# USB_OTG_FS.net
KiCad netlist of a schematic drawn in Altium Designer
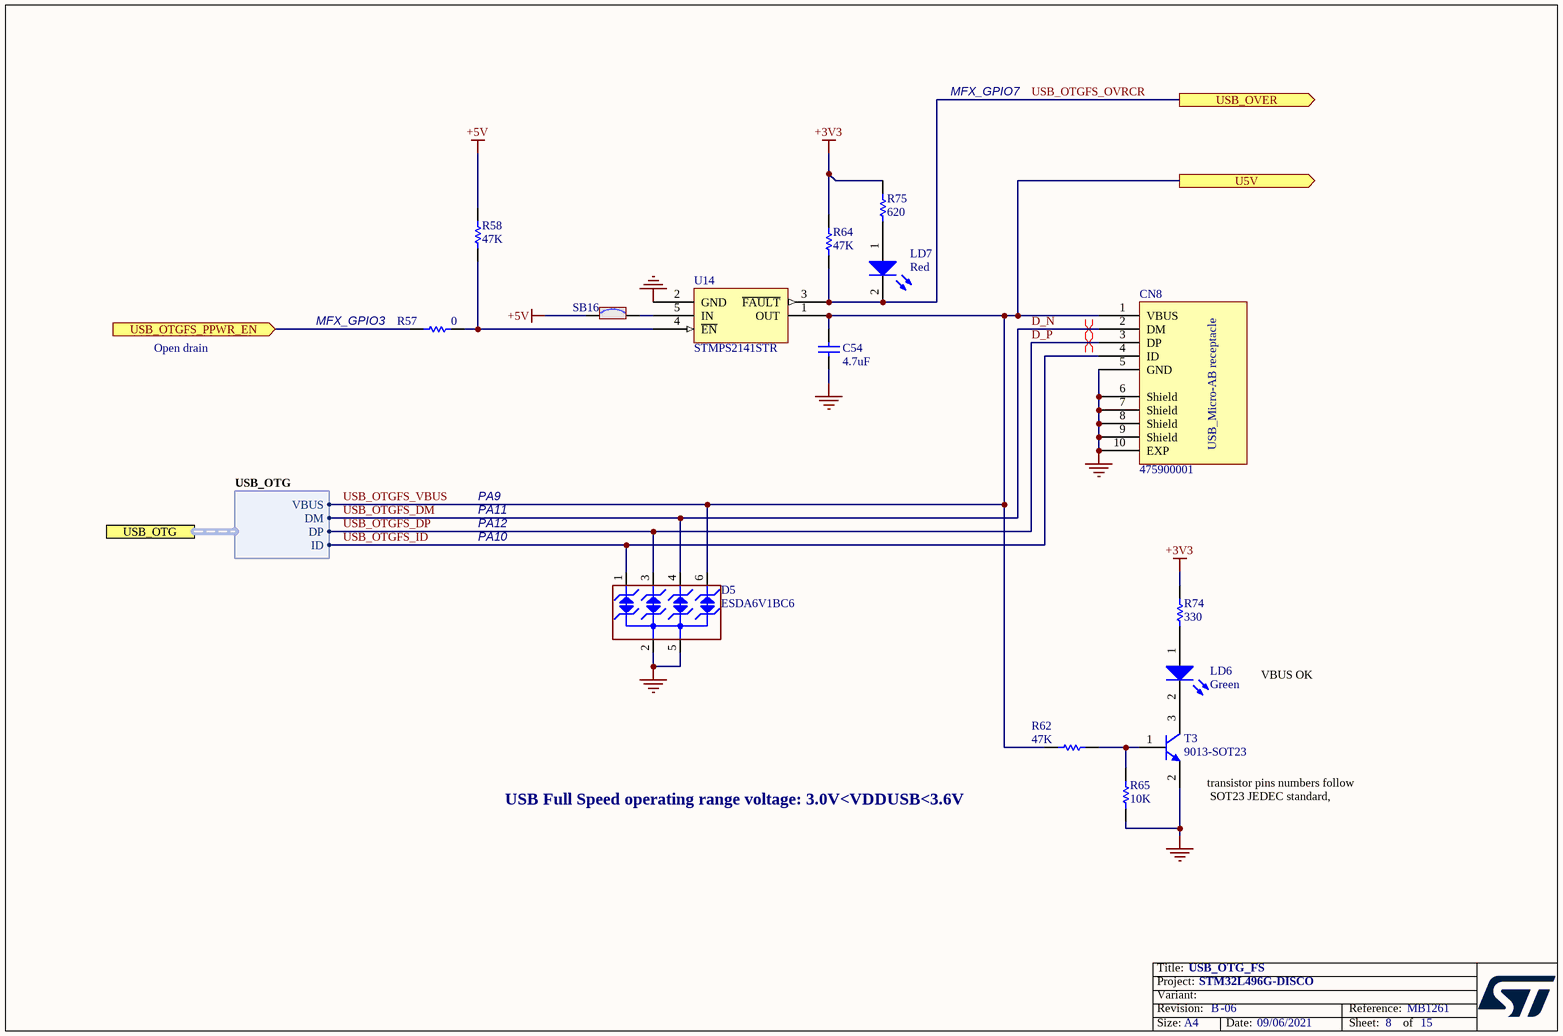
[diagram p0: USB_OTG_FS.SchDoc]

(export (version "E")
  (design (tool "Eeschema 10.0.6"))
  (components
    (comp (ref "C54")
      (value "4.7uF")
      (footprint "0603C")
      (description "Capacitor,4.7uF,16V, X5R,10%,0603")
      (fields (field (name "Comment") "CC0603KRX5R7BB475") (field (name "PUBLISHER") "Altium Limited"))
      (libsource (lib "Miscellaneous Devices") (part "Cap"))
    )
    (comp (ref "CN8")
      (value "475900001")
      (footprint "MOLEX_47590001")
      (libsource (lib "mb1045") (part "475900001"))
    )
    (comp (ref "D5")
      (value "ESDA6V1BC6")
      (footprint "STM-SMEE:SOT23-6L")
      (description "4-line ESD protection")
      (libsource (lib "MB1137") (part "ESDA6V1BC6"))
    )
    (comp (ref "LD6")
      (value "19-213SY6C/S530-E2/TR8LED")
      (footprint "0603D")
      (description "LED,Green,0603")
      (fields (field (name "CORLOR") "Green") (field (name "PUBLISHER") "Altium Limited"))
      (libsource (lib "Miscellaneous Devices") (part "LED2"))
    )
    (comp (ref "LD7")
      (value "19-217/R6C-AL1M2VY/3T")
      (footprint "0603D")
      (description "LED, Red ,0603")
      (fields (field (name "CORLOR") "Red") (field (name "PUBLISHER") "Altium Limited"))
      (libsource (lib "Miscellaneous Devices") (part "LED2"))
    )
    (comp (ref "R57")
      (value "0")
      (footprint "0603R")
      (description "Resistor, 0 ,0603,1%,YAGEO")
      (fields (field (name "Comment") "RC0603JR-070RL") (field (name "PUBLISHER") "Altium Limited"))
      (libsource (lib "Miscellaneous Devices") (part "res1"))
    )
    (comp (ref "R58")
      (value "47K")
      (footprint "0603R")
      (description "Resistor, 47K,0603,1%,YAGEO")
      (fields (field (name "Comment") "RC0603JR-0747KL") (field (name "PUBLISHER") "Altium Limited"))
      (libsource (lib "Miscellaneous Devices") (part "res1"))
    )
    (comp (ref "R62")
      (value "47K")
      (footprint "0603R")
      (description "Resistor, 47K,0603,1%,YAGEO")
      (fields (field (name "Comment") "RC0603JR-0747KL") (field (name "PUBLISHER") "Altium Limited"))
      (libsource (lib "Miscellaneous Devices") (part "res1"))
    )
    (comp (ref "R64")
      (value "47K")
      (footprint "0603R")
      (description "Resistor, 47K,0603,1%,YAGEO")
      (fields (field (name "Comment") "RC0603JR-0747KL") (field (name "PUBLISHER") "Altium Limited"))
      (libsource (lib "Miscellaneous Devices") (part "res1"))
    )
    (comp (ref "R65")
      (value "10K")
      (footprint "0603R")
      (description "Resistor, 10K,0603,1%,YAGEO")
      (fields (field (name "Comment") "RC0603JR-0710KL") (field (name "PUBLISHER") "Altium Limited"))
      (libsource (lib "Miscellaneous Devices") (part "res1"))
    )
    (comp (ref "R74")
      (value "330")
      (footprint "0603R")
      (description "Resistor, 330R , 0603,1%,YAGEO")
      (fields (field (name "Comment") "RC0603JR-07330RL") (field (name "PUBLISHER") "Altium Limited"))
      (libsource (lib "Miscellaneous Devices") (part "res1"))
    )
    (comp (ref "R75")
      (value "620")
      (footprint "0603R")
      (description "Resistor, 620R , 0603,1%,YAGEO")
      (fields (field (name "Comment") "RC0603JR-07620RL") (field (name "PUBLISHER") "Altium Limited"))
      (libsource (lib "Miscellaneous Devices") (part "res1"))
    )
    (comp (ref "SB16")
      (value "Solder Bridge ON")
      (footprint "SB_0603")
      (libsource (lib "MCD_TOOLS") (part "SB_ON"))
    )
    (comp (ref "T3")
      (value "9013-SOT23")
      (footprint "SOT-23")
      (description "NPN Bipolar Transistor")
      (fields (field (name "PUBLISHER") "Altium Limited"))
      (libsource (lib "MB1167") (part "NPN"))
    )
    (comp (ref "U14")
      (value "STMPS2141STR")
      (footprint "SOT23-5")
      (description "Enhanced single channel power switches")
      (libsource (lib "MCD_TOOLS") (part "STMPS2141STR"))
    )
  )
  (nets
    (net (code "2") (name "+3V3") (class "Default")
      (node (ref "R64") (pin "1") (pinfunction "1_1") (pintype "passive"))
      (node (ref "R74") (pin "1") (pinfunction "1_1") (pintype "passive"))
      (node (ref "R75") (pin "1") (pinfunction "1_1") (pintype "passive"))
    )
    (net (code "3") (name "+5V") (class "Default")
      (node (ref "R58") (pin "1") (pinfunction "1_1") (pintype "passive"))
      (node (ref "SB16") (pin "1") (pinfunction "1_1") (pintype "passive"))
    )
    (net (code "4") (name "/D_N") (class "Default")
      (node (ref "CN8") (pin "2") (pinfunction "DM_2") (pintype "passive"))
      (node (ref "D5") (pin "4") (pinfunction "IO3_4") (pintype "passive"))
    )
    (net (code "5") (name "/D_P") (class "Default")
      (node (ref "CN8") (pin "3") (pinfunction "DP_3") (pintype "passive"))
      (node (ref "D5") (pin "3") (pinfunction "GND_3") (pintype "passive"))
    )
    (net (code "6") (name "/USB_OTGFS_ID") (class "Default")
      (node (ref "CN8") (pin "4") (pinfunction "ID_4") (pintype "passive"))
      (node (ref "D5") (pin "1") (pinfunction "IO1_1") (pintype "passive"))
    )
    (net (code "7") (name "/USB_OTGFS_OVRCR") (class "Default")
      (node (ref "LD7") (pin "2") (pinfunction "K_2") (pintype "passive"))
      (node (ref "R64") (pin "2") (pinfunction "2_2") (pintype "passive"))
      (node (ref "U14") (pin "3") (pinfunction "~{FAULT}_3") (pintype "output"))
    )
    (net (code "8") (name "/USB_OTGFS_PPWR_EN") (class "Default")
      (node (ref "R57") (pin "2") (pinfunction "2_2") (pintype "passive"))
    )
    (net (code "9") (name "/USB_OTGFS_VBUS") (class "Default")
      (node (ref "C54") (pin "1") (pinfunction "1_1") (pintype "passive"))
      (node (ref "CN8") (pin "1") (pinfunction "VBUS_1") (pintype "passive"))
      (node (ref "D5") (pin "6") (pinfunction "NC_6") (pintype "passive"))
      (node (ref "R62") (pin "1") (pinfunction "1_1") (pintype "passive"))
      (node (ref "U14") (pin "1") (pinfunction "OUT_1") (pintype "passive"))
    )
    (net (code "11") (name "GND") (class "Default")
      (node (ref "C54") (pin "2") (pinfunction "2_2") (pintype "passive"))
      (node (ref "CN8") (pin "10") (pinfunction "EXP_10") (pintype "passive"))
      (node (ref "CN8") (pin "5") (pinfunction "GND_5") (pintype "passive"))
      (node (ref "CN8") (pin "6") (pinfunction "Shield_6") (pintype "passive"))
      (node (ref "CN8") (pin "7") (pinfunction "Shield_7") (pintype "passive"))
      (node (ref "CN8") (pin "8") (pinfunction "Shield_8") (pintype "passive"))
      (node (ref "CN8") (pin "9") (pinfunction "Shield_9") (pintype "passive"))
      (node (ref "D5") (pin "2") (pinfunction "IO2_2") (pintype "passive"))
      (node (ref "D5") (pin "5") (pinfunction "IO4_5") (pintype "passive"))
      (node (ref "R65") (pin "1") (pinfunction "1_1") (pintype "passive"))
      (node (ref "T3") (pin "2") (pinfunction "E_2") (pintype "passive"))
      (node (ref "U14") (pin "2") (pinfunction "GND_2") (pintype "passive"))
    )
    (net (code "12") (name "Net-(LD6-A)") (class "Default")
      (node (ref "LD6") (pin "1") (pinfunction "A_1") (pintype "passive"))
      (node (ref "R74") (pin "2") (pinfunction "2_2") (pintype "passive"))
    )
    (net (code "13") (name "Net-(LD6-K)") (class "Default")
      (node (ref "LD6") (pin "2") (pinfunction "K_2") (pintype "passive"))
      (node (ref "T3") (pin "3") (pinfunction "C_3") (pintype "passive"))
    )
    (net (code "14") (name "Net-(LD7-A)") (class "Default")
      (node (ref "LD7") (pin "1") (pinfunction "A_1") (pintype "passive"))
      (node (ref "R75") (pin "2") (pinfunction "2_2") (pintype "passive"))
    )
    (net (code "15") (name "Net-(T3-B)") (class "Default")
      (node (ref "R62") (pin "2") (pinfunction "2_2") (pintype "passive"))
      (node (ref "R65") (pin "2") (pinfunction "2_2") (pintype "passive"))
      (node (ref "T3") (pin "1") (pinfunction "B_1") (pintype "passive"))
    )
    (net (code "16") (name "Net-(U14-IN)") (class "Default")
      (node (ref "SB16") (pin "2") (pinfunction "2_2") (pintype "passive"))
      (node (ref "U14") (pin "5") (pinfunction "IN_5") (pintype "passive"))
    )
    (net (code "17") (name "Net-(U14-~{EN})") (class "Default")
      (node (ref "R57") (pin "1") (pinfunction "1_1") (pintype "passive"))
      (node (ref "R58") (pin "2") (pinfunction "2_2") (pintype "passive"))
      (node (ref "U14") (pin "4") (pinfunction "~{EN}_4") (pintype "input"))
    )
  )
)
